# Analog_Pushbutton3.net
KiCad netlist of a schematic drawn in EAGLE
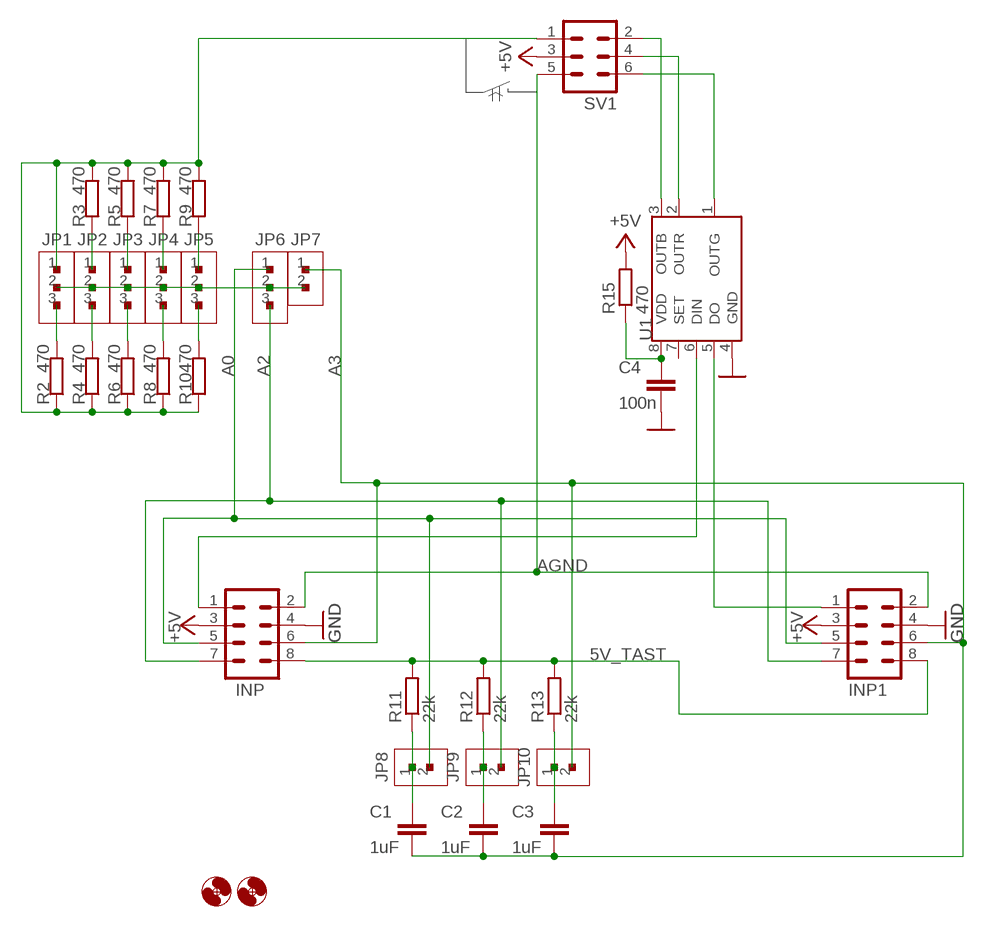
[diagram p0: schematic, sheet 1]

(export (version "E")
  (design (tool "Eeschema 10.0.6"))
  (components
    (comp (ref "C1")
      (value "1uF")
      (footprint "eagle-import:C0603")
      (libsource (lib "eagle-import") (part "C-EUC0603"))
    )
    (comp (ref "C2")
      (value "1uF")
      (footprint "eagle-import:C0603")
      (libsource (lib "eagle-import") (part "C-EUC0603"))
    )
    (comp (ref "C3")
      (value "1uF")
      (footprint "eagle-import:C0603")
      (libsource (lib "eagle-import") (part "C-EUC0603"))
    )
    (comp (ref "C4")
      (value "100n")
      (footprint "eagle-import:C0603")
      (libsource (lib "eagle-import") (part "C-EUC0603"))
    )
    (comp (ref "H1")
      (value "MOUNT-HOLE3.0")
      (footprint "eagle-import:3,0")
      (libsource (lib "eagle-import") (part "MOUNT-HOLE3.0"))
    )
    (comp (ref "H2")
      (value "MOUNT-HOLE3.0")
      (footprint "eagle-import:3,0")
      (libsource (lib "eagle-import") (part "MOUNT-HOLE3.0"))
    )
    (comp (ref "INP")
      (value "CON-HARTING-ML_ML08")
      (footprint "eagle-import:CON-HARTING-ML_ML08")
      (libsource (lib "eagle-import") (part "CON-HARTING-ML_ML08"))
    )
    (comp (ref "INP1")
      (value "CON-HARTING-ML_ML08")
      (footprint "eagle-import:CON-HARTING-ML_ML08")
      (libsource (lib "eagle-import") (part "CON-HARTING-ML_ML08"))
    )
    (comp (ref "JP1")
      (value "PINHD-1X3CB")
      (footprint "eagle-import:1X03-CLEANBIG")
      (libsource (lib "eagle-import") (part "PINHD-1X3CB"))
    )
    (comp (ref "JP2")
      (value "PINHD-1X3CB")
      (footprint "eagle-import:1X03-CLEANBIG")
      (libsource (lib "eagle-import") (part "PINHD-1X3CB"))
    )
    (comp (ref "JP3")
      (value "PINHD-1X3CB")
      (footprint "eagle-import:1X03-CLEANBIG")
      (libsource (lib "eagle-import") (part "PINHD-1X3CB"))
    )
    (comp (ref "JP4")
      (value "PINHD-1X3CB")
      (footprint "eagle-import:1X03-CLEANBIG")
      (libsource (lib "eagle-import") (part "PINHD-1X3CB"))
    )
    (comp (ref "JP5")
      (value "PINHD-1X3CB")
      (footprint "eagle-import:1X03-CLEANBIG")
      (libsource (lib "eagle-import") (part "PINHD-1X3CB"))
    )
    (comp (ref "JP6")
      (value "PINHD-1X3CB")
      (footprint "eagle-import:1X03-CLEANBIG")
      (libsource (lib "eagle-import") (part "PINHD-1X3CB"))
    )
    (comp (ref "JP7")
      (value "PINHD-1X2")
      (footprint "eagle-import:1X02")
      (libsource (lib "eagle-import") (part "PINHD-1X2"))
    )
    (comp (ref "JP8")
      (value "PINHD-1X2")
      (footprint "eagle-import:1X02")
      (libsource (lib "eagle-import") (part "PINHD-1X2"))
    )
    (comp (ref "JP9")
      (value "PINHD-1X2")
      (footprint "eagle-import:1X02")
      (libsource (lib "eagle-import") (part "PINHD-1X2"))
    )
    (comp (ref "JP10")
      (value "PINHD-1X2")
      (footprint "eagle-import:1X02")
      (libsource (lib "eagle-import") (part "PINHD-1X2"))
    )
    (comp (ref "R2")
      (value "470")
      (footprint "eagle-import:R0603")
      (libsource (lib "eagle-import") (part "R-EU_R0603"))
    )
    (comp (ref "R3")
      (value "470")
      (footprint "eagle-import:R0603")
      (libsource (lib "eagle-import") (part "R-EU_R0603"))
    )
    (comp (ref "R4")
      (value "470")
      (footprint "eagle-import:R0603")
      (libsource (lib "eagle-import") (part "R-EU_R0603"))
    )
    (comp (ref "R5")
      (value "470")
      (footprint "eagle-import:R0603")
      (libsource (lib "eagle-import") (part "R-EU_R0603"))
    )
    (comp (ref "R6")
      (value "470")
      (footprint "eagle-import:R0603")
      (libsource (lib "eagle-import") (part "R-EU_R0603"))
    )
    (comp (ref "R7")
      (value "470")
      (footprint "eagle-import:R0603")
      (libsource (lib "eagle-import") (part "R-EU_R0603"))
    )
    (comp (ref "R8")
      (value "470")
      (footprint "eagle-import:R0603")
      (libsource (lib "eagle-import") (part "R-EU_R0603"))
    )
    (comp (ref "R9")
      (value "470")
      (footprint "eagle-import:R0603")
      (libsource (lib "eagle-import") (part "R-EU_R0603"))
    )
    (comp (ref "R10")
      (value "470")
      (footprint "eagle-import:R0603")
      (libsource (lib "eagle-import") (part "R-EU_R0603"))
    )
    (comp (ref "R11")
      (value "22k")
      (footprint "eagle-import:R0603")
      (libsource (lib "eagle-import") (part "R-EU_R0603"))
    )
    (comp (ref "R12")
      (value "22k")
      (footprint "eagle-import:R0603")
      (libsource (lib "eagle-import") (part "R-EU_R0603"))
    )
    (comp (ref "R13")
      (value "22k")
      (footprint "eagle-import:R0603")
      (libsource (lib "eagle-import") (part "R-EU_R0603"))
    )
    (comp (ref "R15")
      (value "470")
      (footprint "eagle-import:R0603")
      (libsource (lib "eagle-import") (part "R-EU_R0603"))
    )
    (comp (ref "SV1")
      (value "CON-HARTING-ML_ML6")
      (footprint "eagle-import:CON-HARTING-ML_ML6")
      (libsource (lib "eagle-import") (part "CON-HARTING-ML_ML6"))
    )
    (comp (ref "U1")
      (value "S3PO_MODUL_WS2811_SOUND_MP3-TF-16P_WS2811_AND_ATTINY_WS2811-ICSOP8")
      (footprint "eagle-import:SOP8")
      (libsource (lib "eagle-import") (part "S3PO_MODUL_WS2811_SOUND_MP3-TF-16P_WS2811_AND_ATTINY_WS2811-ICSOP8"))
    )
  )
  (nets
    (net (code "1") (name "+5V") (class "Default")
      (node (ref "INP") (pin "3") (pinfunction "3_3") (pintype "passive"))
      (node (ref "INP1") (pin "3") (pinfunction "3_3") (pintype "passive"))
      (node (ref "R15") (pin "2") (pinfunction "2_2") (pintype "passive"))
      (node (ref "SV1") (pin "3") (pinfunction "3_3") (pintype "passive"))
    )
    (net (code "2") (name "/5V_TAST") (class "Default")
      (node (ref "INP") (pin "8") (pinfunction "8_8") (pintype "passive"))
      (node (ref "INP1") (pin "8") (pinfunction "8_8") (pintype "passive"))
      (node (ref "R11") (pin "2") (pinfunction "2_2") (pintype "passive"))
      (node (ref "R12") (pin "2") (pinfunction "2_2") (pintype "passive"))
      (node (ref "R13") (pin "2") (pinfunction "2_2") (pintype "passive"))
    )
    (net (code "3") (name "/A0") (class "Default")
      (node (ref "INP") (pin "5") (pinfunction "5_5") (pintype "passive"))
      (node (ref "INP1") (pin "5") (pinfunction "5_5") (pintype "passive"))
      (node (ref "JP6") (pin "1") (pinfunction "1_1") (pintype "passive"))
      (node (ref "JP8") (pin "2") (pinfunction "2_2") (pintype "passive"))
    )
    (net (code "4") (name "/A2") (class "Default")
      (node (ref "INP") (pin "7") (pinfunction "7_7") (pintype "passive"))
      (node (ref "INP1") (pin "7") (pinfunction "7_7") (pintype "passive"))
      (node (ref "JP6") (pin "3") (pinfunction "3_3") (pintype "passive"))
      (node (ref "JP9") (pin "2") (pinfunction "2_2") (pintype "passive"))
    )
    (net (code "5") (name "/A3") (class "Default")
      (node (ref "C1") (pin "2") (pinfunction "2_2") (pintype "passive"))
      (node (ref "C2") (pin "2") (pinfunction "2_2") (pintype "passive"))
      (node (ref "C3") (pin "2") (pinfunction "2_2") (pintype "passive"))
      (node (ref "INP") (pin "6") (pinfunction "6_6") (pintype "passive"))
      (node (ref "INP1") (pin "6") (pinfunction "6_6") (pintype "passive"))
      (node (ref "JP10") (pin "2") (pinfunction "2_2") (pintype "passive"))
      (node (ref "JP7") (pin "1") (pinfunction "1_1") (pintype "passive"))
    )
    (net (code "6") (name "/AGND") (class "Default")
      (node (ref "INP") (pin "2") (pinfunction "2_2") (pintype "passive"))
      (node (ref "INP1") (pin "2") (pinfunction "2_2") (pintype "passive"))
      (node (ref "SV1") (pin "5") (pinfunction "5_5") (pintype "passive"))
    )
    (net (code "7") (name "GND") (class "Default")
      (node (ref "C4") (pin "2") (pinfunction "2_2") (pintype "passive"))
      (node (ref "INP") (pin "4") (pinfunction "4_4") (pintype "passive"))
      (node (ref "INP1") (pin "4") (pinfunction "4_4") (pintype "passive"))
      (node (ref "U1") (pin "4") (pinfunction "GND_4") (pintype "power_in"))
    )
    (net (code "8") (name "Net-(C1-Pad1)") (class "Default")
      (node (ref "C1") (pin "1") (pinfunction "1_1") (pintype "passive"))
      (node (ref "JP8") (pin "1") (pinfunction "1_1") (pintype "passive"))
      (node (ref "R11") (pin "1") (pinfunction "1_1") (pintype "passive"))
    )
    (net (code "9") (name "Net-(C2-Pad1)") (class "Default")
      (node (ref "C2") (pin "1") (pinfunction "1_1") (pintype "passive"))
      (node (ref "JP9") (pin "1") (pinfunction "1_1") (pintype "passive"))
      (node (ref "R12") (pin "1") (pinfunction "1_1") (pintype "passive"))
    )
    (net (code "10") (name "Net-(C3-Pad1)") (class "Default")
      (node (ref "C3") (pin "1") (pinfunction "1_1") (pintype "passive"))
      (node (ref "JP10") (pin "1") (pinfunction "1_1") (pintype "passive"))
      (node (ref "R13") (pin "1") (pinfunction "1_1") (pintype "passive"))
    )
    (net (code "11") (name "Net-(JP1-Pad1)") (class "Default")
      (node (ref "JP1") (pin "1") (pinfunction "1_1") (pintype "passive"))
      (node (ref "R10") (pin "1") (pinfunction "1_1") (pintype "passive"))
      (node (ref "R2") (pin "1") (pinfunction "1_1") (pintype "passive"))
      (node (ref "R3") (pin "2") (pinfunction "2_2") (pintype "passive"))
      (node (ref "R4") (pin "1") (pinfunction "1_1") (pintype "passive"))
      (node (ref "R5") (pin "2") (pinfunction "2_2") (pintype "passive"))
      (node (ref "R6") (pin "1") (pinfunction "1_1") (pintype "passive"))
      (node (ref "R7") (pin "2") (pinfunction "2_2") (pintype "passive"))
      (node (ref "R8") (pin "1") (pinfunction "1_1") (pintype "passive"))
      (node (ref "R9") (pin "2") (pinfunction "2_2") (pintype "passive"))
      (node (ref "SV1") (pin "1") (pinfunction "1_1") (pintype "passive"))
    )
    (net (code "12") (name "Net-(JP1-Pad2)") (class "Default")
      (node (ref "JP1") (pin "2") (pinfunction "2_2") (pintype "passive"))
      (node (ref "JP2") (pin "2") (pinfunction "2_2") (pintype "passive"))
      (node (ref "JP3") (pin "2") (pinfunction "2_2") (pintype "passive"))
      (node (ref "JP4") (pin "2") (pinfunction "2_2") (pintype "passive"))
      (node (ref "JP5") (pin "2") (pinfunction "2_2") (pintype "passive"))
      (node (ref "JP6") (pin "2") (pinfunction "2_2") (pintype "passive"))
      (node (ref "JP7") (pin "2") (pinfunction "2_2") (pintype "passive"))
    )
    (net (code "13") (name "Net-(JP1-Pad3)") (class "Default")
      (node (ref "JP1") (pin "3") (pinfunction "3_3") (pintype "passive"))
      (node (ref "R2") (pin "2") (pinfunction "2_2") (pintype "passive"))
    )
    (net (code "14") (name "Net-(JP2-Pad1)") (class "Default")
      (node (ref "JP2") (pin "1") (pinfunction "1_1") (pintype "passive"))
      (node (ref "R3") (pin "1") (pinfunction "1_1") (pintype "passive"))
    )
    (net (code "15") (name "Net-(JP2-Pad3)") (class "Default")
      (node (ref "JP2") (pin "3") (pinfunction "3_3") (pintype "passive"))
      (node (ref "R4") (pin "2") (pinfunction "2_2") (pintype "passive"))
    )
    (net (code "16") (name "Net-(JP3-Pad1)") (class "Default")
      (node (ref "JP3") (pin "1") (pinfunction "1_1") (pintype "passive"))
      (node (ref "R5") (pin "1") (pinfunction "1_1") (pintype "passive"))
    )
    (net (code "17") (name "Net-(JP3-Pad3)") (class "Default")
      (node (ref "JP3") (pin "3") (pinfunction "3_3") (pintype "passive"))
      (node (ref "R6") (pin "2") (pinfunction "2_2") (pintype "passive"))
    )
    (net (code "18") (name "Net-(JP4-Pad1)") (class "Default")
      (node (ref "JP4") (pin "1") (pinfunction "1_1") (pintype "passive"))
      (node (ref "R7") (pin "1") (pinfunction "1_1") (pintype "passive"))
    )
    (net (code "19") (name "Net-(JP4-Pad3)") (class "Default")
      (node (ref "JP4") (pin "3") (pinfunction "3_3") (pintype "passive"))
      (node (ref "R8") (pin "2") (pinfunction "2_2") (pintype "passive"))
    )
    (net (code "20") (name "Net-(JP5-Pad1)") (class "Default")
      (node (ref "JP5") (pin "1") (pinfunction "1_1") (pintype "passive"))
      (node (ref "R9") (pin "1") (pinfunction "1_1") (pintype "passive"))
    )
    (net (code "21") (name "Net-(JP5-Pad3)") (class "Default")
      (node (ref "JP5") (pin "3") (pinfunction "3_3") (pintype "passive"))
      (node (ref "R10") (pin "2") (pinfunction "2_2") (pintype "passive"))
    )
    (net (code "22") (name "Net-(U1-DIN)") (class "Default")
      (node (ref "INP") (pin "1") (pinfunction "1_1") (pintype "passive"))
      (node (ref "U1") (pin "6") (pinfunction "DIN_6") (pintype "input"))
    )
    (net (code "23") (name "Net-(U1-DO)") (class "Default")
      (node (ref "INP1") (pin "1") (pinfunction "1_1") (pintype "passive"))
      (node (ref "U1") (pin "5") (pinfunction "DO_5") (pintype "output"))
    )
    (net (code "24") (name "Net-(U1-OUTB)") (class "Default")
      (node (ref "SV1") (pin "2") (pinfunction "2_2") (pintype "passive"))
      (node (ref "U1") (pin "3") (pinfunction "OUTB_3") (pintype "open_collector"))
    )
    (net (code "25") (name "Net-(U1-OUTG)") (class "Default")
      (node (ref "SV1") (pin "6") (pinfunction "6_6") (pintype "passive"))
      (node (ref "U1") (pin "1") (pinfunction "OUTG_1") (pintype "open_collector"))
    )
    (net (code "26") (name "Net-(U1-OUTR)") (class "Default")
      (node (ref "SV1") (pin "4") (pinfunction "4_4") (pintype "passive"))
      (node (ref "U1") (pin "2") (pinfunction "OUTR_2") (pintype "open_collector"))
    )
    (net (code "27") (name "Net-(U1-VDD)") (class "Default")
      (node (ref "C4") (pin "1") (pinfunction "1_1") (pintype "passive"))
      (node (ref "R15") (pin "1") (pinfunction "1_1") (pintype "passive"))
      (node (ref "U1") (pin "8") (pinfunction "VDD_8") (pintype "power_in"))
    )
    (net (code "28") (name "unconnected-(U1-SET-Pad7)") (class "Default")
      (node (ref "U1") (pin "7") (pinfunction "SET_7") (pintype "bidirectional"))
    )
  )
)
